# Rev1.net
KiCad netlist of a schematic drawn in EAGLE
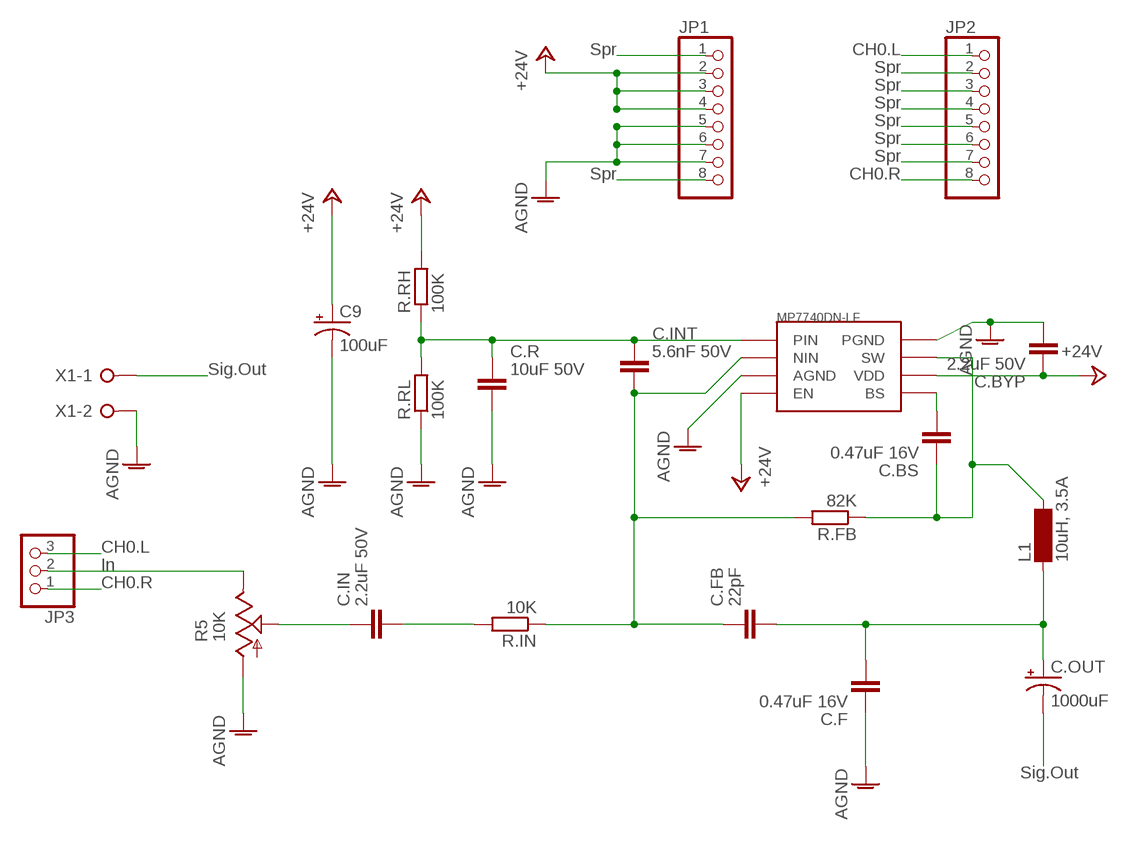
[diagram p0: schematic, sheet 1]

(export (version "E")
  (design (tool "Eeschema 10.0.6"))
  (components
    (comp (ref "C.BS")
      (value "0.47uF 16V")
      (footprint "eagle-import:C805")
      (libsource (lib "eagle-import") (part "CAPACITOR_NPOL-0805"))
    )
    (comp (ref "C.BYP")
      (value "2.2uF 50V")
      (footprint "eagle-import:C805")
      (libsource (lib "eagle-import") (part "CAPACITOR_NPOL-0805"))
    )
    (comp (ref "C.F")
      (value "0.47uF 16V")
      (footprint "eagle-import:C805")
      (libsource (lib "eagle-import") (part "CAPACITOR_NPOL-0805"))
    )
    (comp (ref "C.FB")
      (value "22pF")
      (footprint "eagle-import:C603")
      (libsource (lib "eagle-import") (part "CAPACITOR_NPOL-0603"))
    )
    (comp (ref "C.IN")
      (value "2.2uF 50V")
      (footprint "eagle-import:C805")
      (libsource (lib "eagle-import") (part "CAPACITOR_NPOL-0805"))
    )
    (comp (ref "C.INT")
      (value "5.6nF 50V")
      (footprint "eagle-import:C603")
      (libsource (lib "eagle-import") (part "CAPACITOR_NPOL-0603"))
    )
    (comp (ref "C.OUT")
      (value "1000uF")
      (footprint "eagle-import:E5-4")
      (libsource (lib "eagle-import") (part "CPOL-USE5-4"))
    )
    (comp (ref "C.R")
      (value "10uF 50V")
      (footprint "eagle-import:C1206")
      (libsource (lib "eagle-import") (part "CAPACITOR_NPOL-1206"))
    )
    (comp (ref "C9")
      (value "100uF")
      (footprint "eagle-import:E5-4")
      (libsource (lib "eagle-import") (part "CPOL-USE5-4"))
    )
    (comp (ref "JP1")
      (value "PINHD-1X8")
      (footprint "eagle-import:1X08")
      (libsource (lib "eagle-import") (part "PINHD-1X8"))
    )
    (comp (ref "JP2")
      (value "PINHD-1X8")
      (footprint "eagle-import:1X08")
      (libsource (lib "eagle-import") (part "PINHD-1X8"))
    )
    (comp (ref "JP3")
      (value "PINHD-1X3")
      (footprint "eagle-import:1X03")
      (libsource (lib "eagle-import") (part "PINHD-1X3"))
    )
    (comp (ref "L1")
      (value "10uH, 3.5A")
      (footprint "eagle-import:BS11")
      (libsource (lib "eagle-import") (part "BS11"))
    )
    (comp (ref "R.FB")
      (value "82K")
      (footprint "eagle-import:R805")
      (libsource (lib "eagle-import") (part "RESISTOR-0805R805"))
    )
    (comp (ref "R.IN")
      (value "10K")
      (footprint "eagle-import:R805")
      (libsource (lib "eagle-import") (part "RESISTOR-0805R805"))
    )
    (comp (ref "R.RH")
      (value "100K")
      (footprint "eagle-import:R603")
      (libsource (lib "eagle-import") (part "RESISTOR-0603"))
    )
    (comp (ref "R.RL")
      (value "100K")
      (footprint "eagle-import:R603")
      (libsource (lib "eagle-import") (part "RESISTOR-0603"))
    )
    (comp (ref "R5")
      (value "10K")
      (footprint "eagle-import:PT-10S")
      (libsource (lib "eagle-import") (part "TRIM_US-PT-10S"))
    )
    (comp (ref "U$1")
      (value "MP7740DN-LF")
      (footprint "eagle-import:SOIC8")
      (libsource (lib "eagle-import") (part "MP7740DN-LF"))
    )
    (comp (ref "X1")
      (value "W237-02P")
      (footprint "eagle-import:W237-132")
      (libsource (lib "eagle-import") (part "W237-02P"))
    )
  )
  (nets
    (net (code "1") (name "+24V") (class "Default")
      (node (ref "C.BYP") (pin "1") (pinfunction "1_1") (pintype "passive"))
      (node (ref "C9") (pin "+") (pinfunction "+_+") (pintype "passive"))
      (node (ref "JP1") (pin "2") (pinfunction "2_2") (pintype "passive"))
      (node (ref "JP1") (pin "3") (pinfunction "3_3") (pintype "passive"))
      (node (ref "JP1") (pin "4") (pinfunction "4_4") (pintype "passive"))
      (node (ref "R.RH") (pin "2") (pinfunction "2_2") (pintype "passive"))
      (node (ref "U$1") (pin "4") (pinfunction "EN_4") (pintype "bidirectional"))
      (node (ref "U$1") (pin "6") (pinfunction "VDD_6") (pintype "bidirectional"))
    )
    (net (code "2") (name "/CH0.L") (class "Default")
      (node (ref "JP2") (pin "1") (pinfunction "1_1") (pintype "passive"))
      (node (ref "JP3") (pin "3") (pinfunction "3_3") (pintype "passive"))
    )
    (net (code "3") (name "/CH0.R") (class "Default")
      (node (ref "JP2") (pin "8") (pinfunction "8_8") (pintype "passive"))
      (node (ref "JP3") (pin "1") (pinfunction "1_1") (pintype "passive"))
    )
    (net (code "4") (name "/SIGOUT") (class "Default")
      (node (ref "C.OUT") (pin "-") (pinfunction "-_-") (pintype "passive"))
      (node (ref "X1") (pin "1") (pinfunction "KL_1") (pintype "passive"))
    )
    (net (code "5") (name "AGND") (class "Default")
      (node (ref "C.BYP") (pin "2") (pinfunction "2_2") (pintype "passive"))
      (node (ref "C.F") (pin "1") (pinfunction "1_1") (pintype "passive"))
      (node (ref "C.R") (pin "2") (pinfunction "2_2") (pintype "passive"))
      (node (ref "C9") (pin "-") (pinfunction "-_-") (pintype "passive"))
      (node (ref "JP1") (pin "5") (pinfunction "5_5") (pintype "passive"))
      (node (ref "JP1") (pin "6") (pinfunction "6_6") (pintype "passive"))
      (node (ref "JP1") (pin "7") (pinfunction "7_7") (pintype "passive"))
      (node (ref "R.RL") (pin "1") (pinfunction "1_1") (pintype "passive"))
      (node (ref "R5") (pin "A") (pinfunction "A_A") (pintype "passive"))
      (node (ref "U$1") (pin "3") (pinfunction "AGND_3") (pintype "bidirectional"))
      (node (ref "U$1") (pin "8") (pinfunction "PGND_8") (pintype "bidirectional"))
      (node (ref "X1") (pin "2") (pinfunction "KL_2") (pintype "passive"))
    )
    (net (code "6") (name "Net-(C.F-Pad2)") (class "Default")
      (node (ref "C.F") (pin "2") (pinfunction "2_2") (pintype "passive"))
      (node (ref "C.FB") (pin "2") (pinfunction "2_2") (pintype "passive"))
      (node (ref "C.OUT") (pin "+") (pinfunction "+_+") (pintype "passive"))
      (node (ref "L1") (pin "1") (pinfunction "1_1") (pintype "passive"))
    )
    (net (code "7") (name "Net-(C.IN-Pad1)") (class "Default")
      (node (ref "C.IN") (pin "1") (pinfunction "1_1") (pintype "passive"))
      (node (ref "R5") (pin "S") (pinfunction "S_S") (pintype "passive"))
    )
    (net (code "8") (name "Net-(C.IN-Pad2)") (class "Default")
      (node (ref "C.IN") (pin "2") (pinfunction "2_2") (pintype "passive"))
      (node (ref "R.IN") (pin "2") (pinfunction "2_2") (pintype "passive"))
    )
    (net (code "9") (name "Net-(JP3-Pad2)") (class "Default")
      (node (ref "JP3") (pin "2") (pinfunction "2_2") (pintype "passive"))
      (node (ref "R5") (pin "E") (pinfunction "E_E") (pintype "passive"))
    )
    (net (code "10") (name "Net-(U$1-BS)") (class "Default")
      (node (ref "C.BS") (pin "2") (pinfunction "2_2") (pintype "passive"))
      (node (ref "U$1") (pin "5") (pinfunction "BS_5") (pintype "bidirectional"))
    )
    (net (code "11") (name "Net-(U$1-NIN)") (class "Default")
      (node (ref "C.FB") (pin "1") (pinfunction "1_1") (pintype "passive"))
      (node (ref "C.INT") (pin "2") (pinfunction "2_2") (pintype "passive"))
      (node (ref "R.FB") (pin "2") (pinfunction "2_2") (pintype "passive"))
      (node (ref "R.IN") (pin "1") (pinfunction "1_1") (pintype "passive"))
      (node (ref "U$1") (pin "2") (pinfunction "NIN_2") (pintype "bidirectional"))
    )
    (net (code "12") (name "Net-(U$1-PIN)") (class "Default")
      (node (ref "C.INT") (pin "1") (pinfunction "1_1") (pintype "passive"))
      (node (ref "C.R") (pin "1") (pinfunction "1_1") (pintype "passive"))
      (node (ref "R.RH") (pin "1") (pinfunction "1_1") (pintype "passive"))
      (node (ref "R.RL") (pin "2") (pinfunction "2_2") (pintype "passive"))
      (node (ref "U$1") (pin "1") (pinfunction "PIN_1") (pintype "bidirectional"))
    )
    (net (code "13") (name "Net-(U$1-SW)") (class "Default")
      (node (ref "C.BS") (pin "1") (pinfunction "1_1") (pintype "passive"))
      (node (ref "L1") (pin "2") (pinfunction "2_2") (pintype "passive"))
      (node (ref "R.FB") (pin "1") (pinfunction "1_1") (pintype "passive"))
      (node (ref "U$1") (pin "7") (pinfunction "SW_7") (pintype "bidirectional"))
    )
    (net (code "14") (name "unconnected-(JP1-Pad1)") (class "Default")
      (node (ref "JP1") (pin "1") (pinfunction "1_1") (pintype "passive"))
    )
    (net (code "15") (name "unconnected-(JP1-Pad8)") (class "Default")
      (node (ref "JP1") (pin "8") (pinfunction "8_8") (pintype "passive"))
    )
    (net (code "16") (name "unconnected-(JP2-Pad2)") (class "Default")
      (node (ref "JP2") (pin "2") (pinfunction "2_2") (pintype "passive"))
    )
    (net (code "17") (name "unconnected-(JP2-Pad3)") (class "Default")
      (node (ref "JP2") (pin "3") (pinfunction "3_3") (pintype "passive"))
    )
    (net (code "18") (name "unconnected-(JP2-Pad4)") (class "Default")
      (node (ref "JP2") (pin "4") (pinfunction "4_4") (pintype "passive"))
    )
    (net (code "19") (name "unconnected-(JP2-Pad5)") (class "Default")
      (node (ref "JP2") (pin "5") (pinfunction "5_5") (pintype "passive"))
    )
    (net (code "20") (name "unconnected-(JP2-Pad6)") (class "Default")
      (node (ref "JP2") (pin "6") (pinfunction "6_6") (pintype "passive"))
    )
    (net (code "21") (name "unconnected-(JP2-Pad7)") (class "Default")
      (node (ref "JP2") (pin "7") (pinfunction "7_7") (pintype "passive"))
    )
  )
)
